# MXM_Connector.net
KiCad netlist of a schematic drawn in Altium Designer
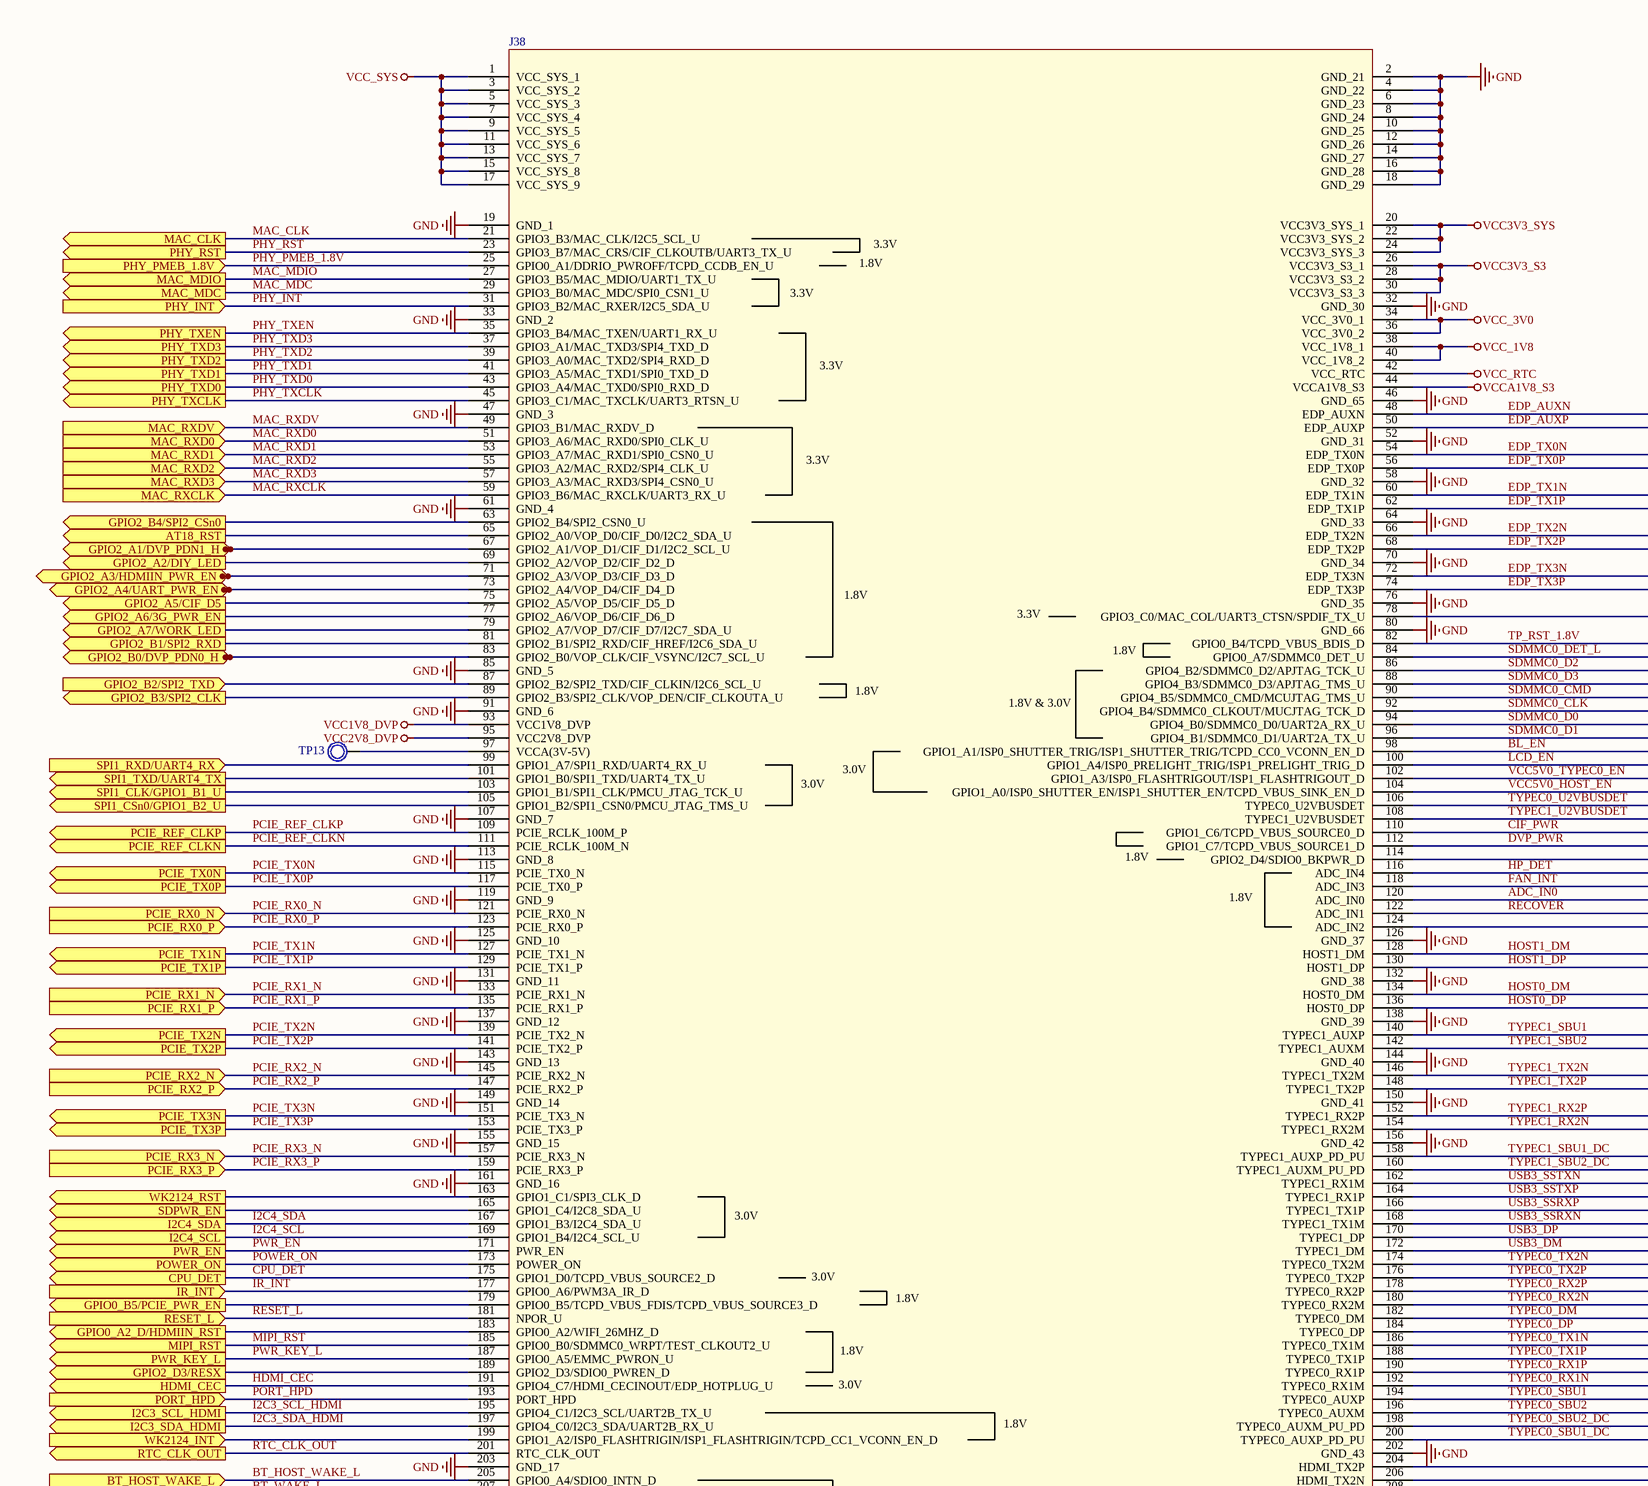
[diagram p0: MXM_Connector.SchDoc, top left]
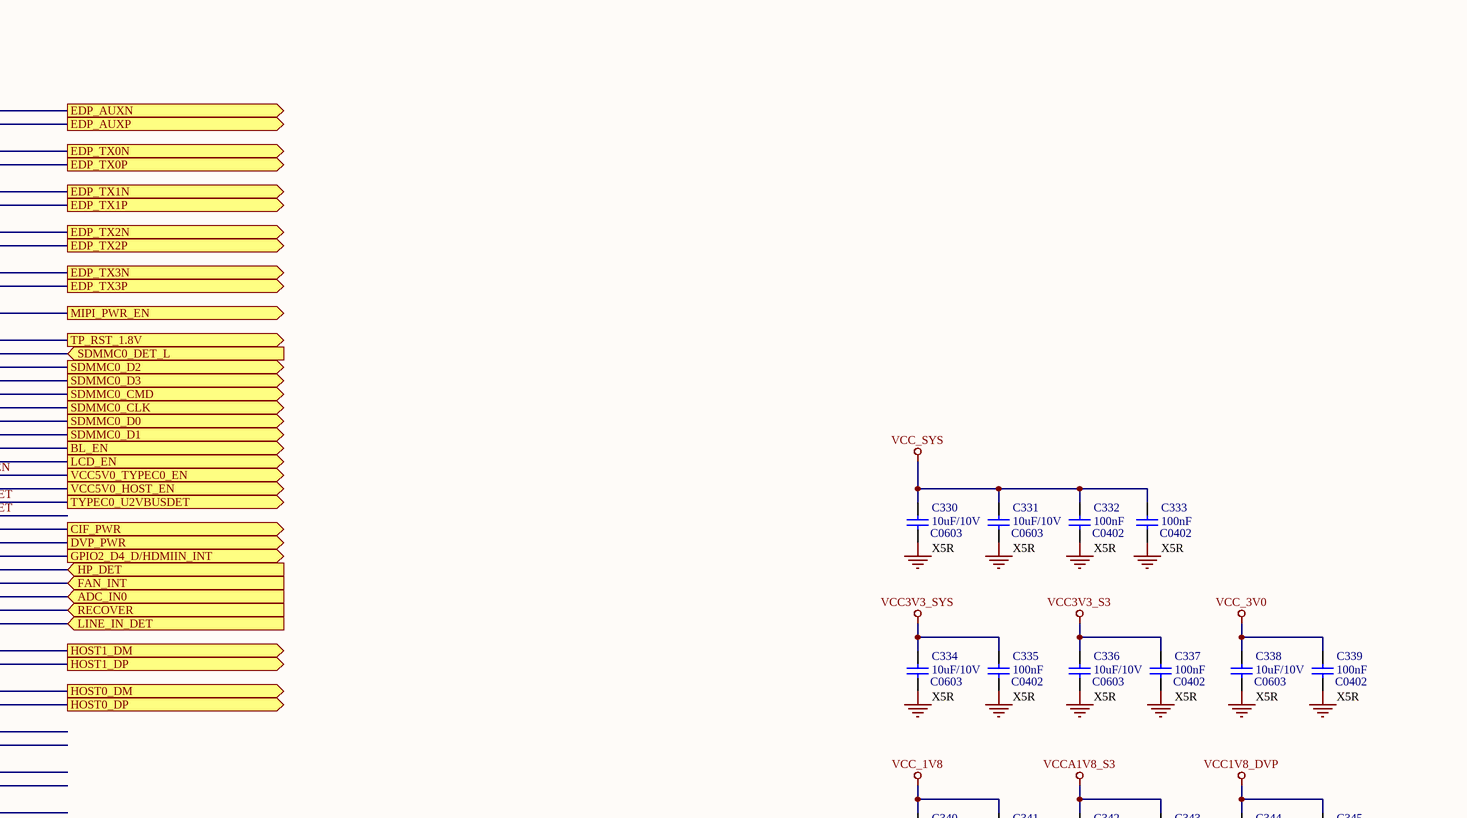
[diagram p1: MXM_Connector.SchDoc, top right]
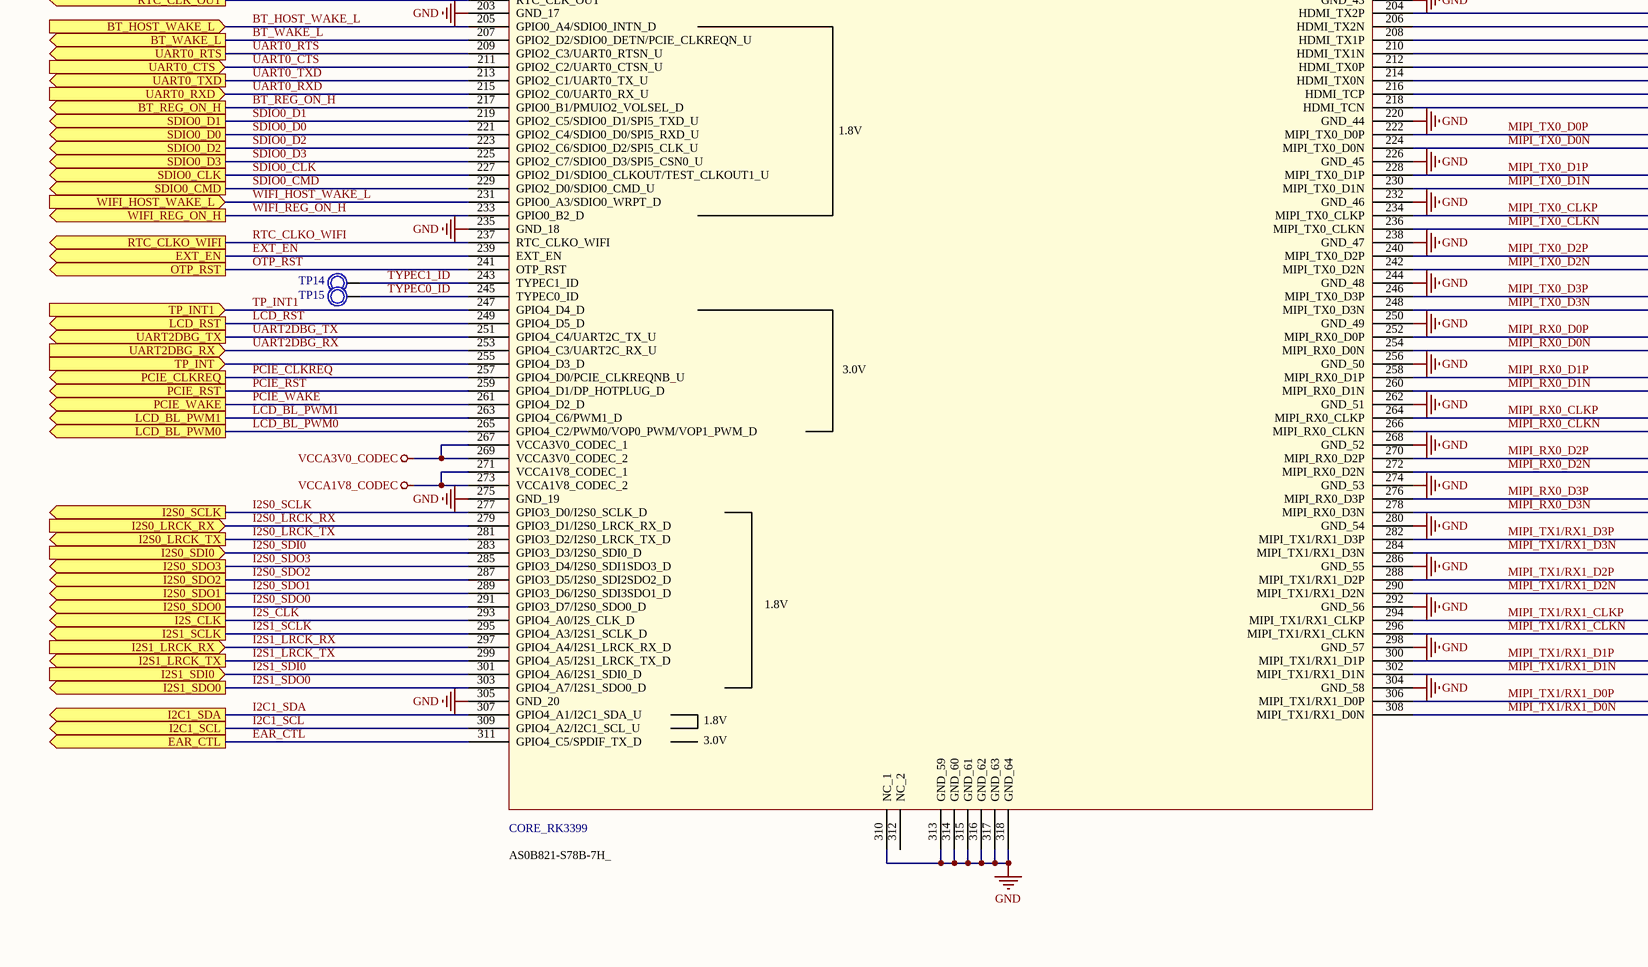
[diagram p2: MXM_Connector.SchDoc, bottom left]
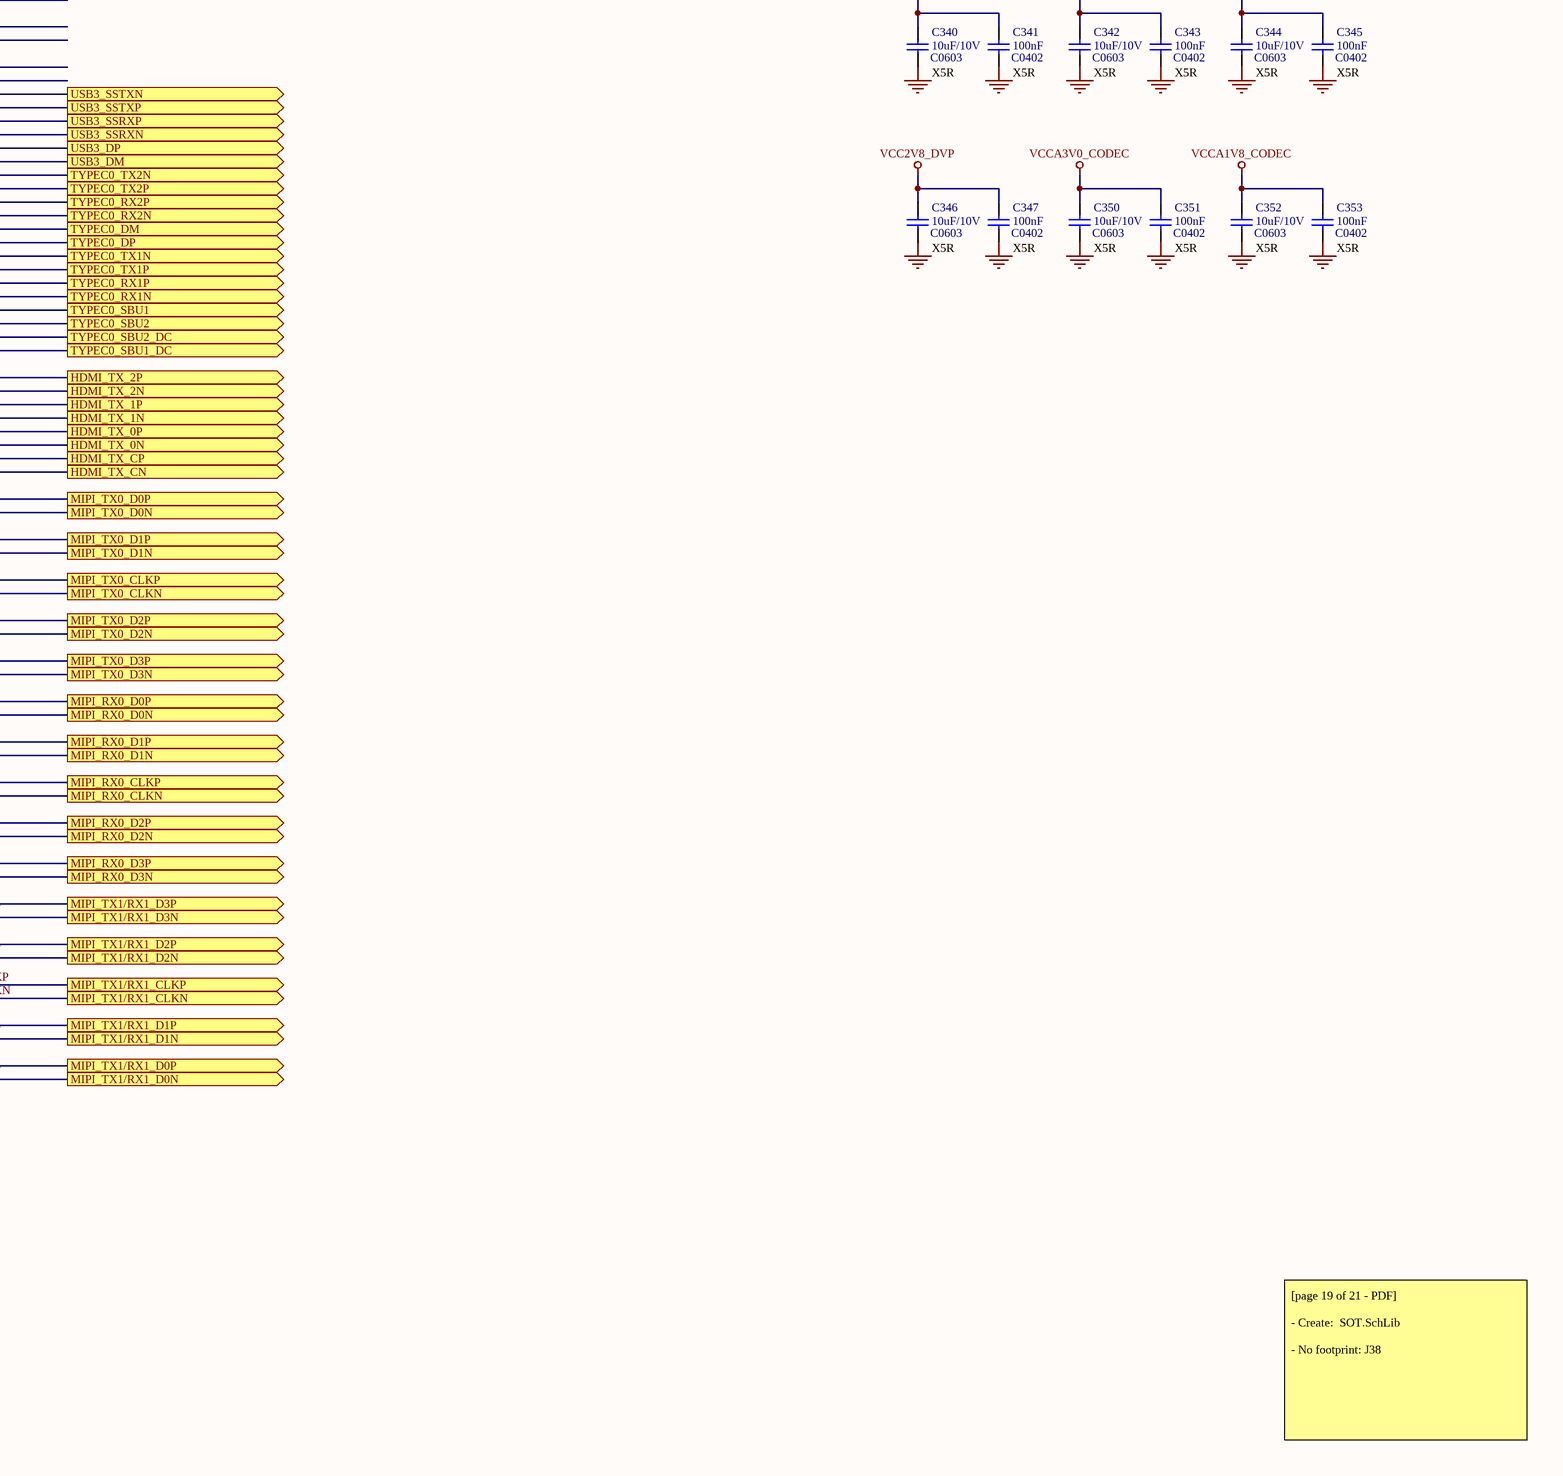
[diagram p3: MXM_Connector.SchDoc, bottom right]

(export (version "E")
  (design (tool "Eeschema 10.0.6"))
  (components
    (comp (ref "C330")
      (value "C0603")
      (footprint "C 0603")
      (description "Capacitor")
      (fields
        (field (name "ALTIUM_VALUE") "10uF/10V")
        (field (name "ALTIUM_UNNAMED_1") "X5R")
        (field (name "PUBLISHER") "Altium Limited")
      )
      (libsource (lib "Miscellaneous Devices") (part "Cap"))
    )
    (comp (ref "C331")
      (value "C0603")
      (footprint "C 0603")
      (description "Capacitor")
      (fields
        (field (name "ALTIUM_VALUE") "10uF/10V")
        (field (name "ALTIUM_UNNAMED_1") "X5R")
        (field (name "PUBLISHER") "Altium Limited")
      )
      (libsource (lib "Miscellaneous Devices") (part "Cap"))
    )
    (comp (ref "C332")
      (value "C0402")
      (footprint "C 0402")
      (description "Capacitor")
      (fields
        (field (name "ALTIUM_VALUE") "100nF")
        (field (name "ALTIUM_UNNAMED_1") "X5R")
        (field (name "PUBLISHER") "Altium Limited")
      )
      (libsource (lib "Miscellaneous Devices") (part "Cap"))
    )
    (comp (ref "C333")
      (value "C0402")
      (footprint "C 0402")
      (description "Capacitor")
      (fields
        (field (name "ALTIUM_VALUE") "100nF")
        (field (name "ALTIUM_UNNAMED_1") "X5R")
        (field (name "PUBLISHER") "Altium Limited")
      )
      (libsource (lib "Miscellaneous Devices") (part "Cap"))
    )
    (comp (ref "C334")
      (value "C0603")
      (footprint "C 0603")
      (description "Capacitor")
      (fields
        (field (name "ALTIUM_VALUE") "10uF/10V")
        (field (name "ALTIUM_UNNAMED_1") "X5R")
        (field (name "PUBLISHER") "Altium Limited")
      )
      (libsource (lib "Miscellaneous Devices") (part "Cap"))
    )
    (comp (ref "C335")
      (value "C0402")
      (footprint "C 0402")
      (description "Capacitor")
      (fields
        (field (name "ALTIUM_VALUE") "100nF")
        (field (name "ALTIUM_UNNAMED_1") "X5R")
        (field (name "PUBLISHER") "Altium Limited")
      )
      (libsource (lib "Miscellaneous Devices") (part "Cap"))
    )
    (comp (ref "C336")
      (value "C0603")
      (footprint "C 0603")
      (description "Capacitor")
      (fields
        (field (name "ALTIUM_VALUE") "10uF/10V")
        (field (name "ALTIUM_UNNAMED_1") "X5R")
        (field (name "PUBLISHER") "Altium Limited")
      )
      (libsource (lib "Miscellaneous Devices") (part "Cap"))
    )
    (comp (ref "C337")
      (value "C0402")
      (footprint "C 0402")
      (description "Capacitor")
      (fields
        (field (name "ALTIUM_VALUE") "100nF")
        (field (name "ALTIUM_UNNAMED_1") "X5R")
        (field (name "PUBLISHER") "Altium Limited")
      )
      (libsource (lib "Miscellaneous Devices") (part "Cap"))
    )
    (comp (ref "C338")
      (value "C0603")
      (footprint "C 0603")
      (description "Capacitor")
      (fields
        (field (name "ALTIUM_VALUE") "10uF/10V")
        (field (name "ALTIUM_UNNAMED_1") "X5R")
        (field (name "PUBLISHER") "Altium Limited")
      )
      (libsource (lib "Miscellaneous Devices") (part "Cap"))
    )
    (comp (ref "C339")
      (value "C0402")
      (footprint "C 0402")
      (description "Capacitor")
      (fields
        (field (name "ALTIUM_VALUE") "100nF")
        (field (name "ALTIUM_UNNAMED_1") "X5R")
        (field (name "PUBLISHER") "Altium Limited")
      )
      (libsource (lib "Miscellaneous Devices") (part "Cap"))
    )
    (comp (ref "C340")
      (value "C0603")
      (footprint "C 0603")
      (description "Capacitor")
      (fields
        (field (name "ALTIUM_VALUE") "10uF/10V")
        (field (name "ALTIUM_UNNAMED_1") "X5R")
        (field (name "PUBLISHER") "Altium Limited")
      )
      (libsource (lib "Miscellaneous Devices") (part "Cap"))
    )
    (comp (ref "C341")
      (value "C0402")
      (footprint "C 0402")
      (description "Capacitor")
      (fields
        (field (name "ALTIUM_VALUE") "100nF")
        (field (name "ALTIUM_UNNAMED_1") "X5R")
        (field (name "PUBLISHER") "Altium Limited")
      )
      (libsource (lib "Miscellaneous Devices") (part "Cap"))
    )
    (comp (ref "C342")
      (value "C0603")
      (footprint "C 0603")
      (description "Capacitor")
      (fields
        (field (name "ALTIUM_VALUE") "10uF/10V")
        (field (name "ALTIUM_UNNAMED_1") "X5R")
        (field (name "PUBLISHER") "Altium Limited")
      )
      (libsource (lib "Miscellaneous Devices") (part "Cap"))
    )
    (comp (ref "C343")
      (value "C0402")
      (footprint "C 0402")
      (description "Capacitor")
      (fields
        (field (name "ALTIUM_VALUE") "100nF")
        (field (name "ALTIUM_UNNAMED_1") "X5R")
        (field (name "PUBLISHER") "Altium Limited")
      )
      (libsource (lib "Miscellaneous Devices") (part "Cap"))
    )
    (comp (ref "C344")
      (value "C0603")
      (footprint "C 0603")
      (description "Capacitor")
      (fields
        (field (name "ALTIUM_VALUE") "10uF/10V")
        (field (name "ALTIUM_UNNAMED_1") "X5R")
        (field (name "PUBLISHER") "Altium Limited")
      )
      (libsource (lib "Miscellaneous Devices") (part "Cap"))
    )
    (comp (ref "C345")
      (value "C0402")
      (footprint "C 0402")
      (description "Capacitor")
      (fields
        (field (name "ALTIUM_VALUE") "100nF")
        (field (name "ALTIUM_UNNAMED_1") "X5R")
        (field (name "PUBLISHER") "Altium Limited")
      )
      (libsource (lib "Miscellaneous Devices") (part "Cap"))
    )
    (comp (ref "C346")
      (value "C0603")
      (footprint "C 0603")
      (description "Capacitor")
      (fields
        (field (name "ALTIUM_VALUE") "10uF/10V")
        (field (name "ALTIUM_UNNAMED_1") "X5R")
        (field (name "PUBLISHER") "Altium Limited")
      )
      (libsource (lib "Miscellaneous Devices") (part "Cap"))
    )
    (comp (ref "C347")
      (value "C0402")
      (footprint "C 0402")
      (description "Capacitor")
      (fields
        (field (name "ALTIUM_VALUE") "100nF")
        (field (name "ALTIUM_UNNAMED_1") "X5R")
        (field (name "PUBLISHER") "Altium Limited")
      )
      (libsource (lib "Miscellaneous Devices") (part "Cap"))
    )
    (comp (ref "C350")
      (value "C0603")
      (footprint "C 0603")
      (description "Capacitor")
      (fields
        (field (name "ALTIUM_VALUE") "10uF/10V")
        (field (name "ALTIUM_UNNAMED_1") "X5R")
        (field (name "PUBLISHER") "Altium Limited")
      )
      (libsource (lib "Miscellaneous Devices") (part "Cap"))
    )
    (comp (ref "C351")
      (value "C0402")
      (footprint "C 0402")
      (description "Capacitor")
      (fields
        (field (name "ALTIUM_VALUE") "100nF")
        (field (name "ALTIUM_UNNAMED_1") "X5R")
        (field (name "PUBLISHER") "Altium Limited")
      )
      (libsource (lib "Miscellaneous Devices") (part "Cap"))
    )
    (comp (ref "C352")
      (value "C0603")
      (footprint "C 0603")
      (description "Capacitor")
      (fields
        (field (name "ALTIUM_VALUE") "10uF/10V")
        (field (name "ALTIUM_UNNAMED_1") "X5R")
        (field (name "PUBLISHER") "Altium Limited")
      )
      (libsource (lib "Miscellaneous Devices") (part "Cap"))
    )
    (comp (ref "C353")
      (value "C0402")
      (footprint "C 0402")
      (description "Capacitor")
      (fields
        (field (name "ALTIUM_VALUE") "100nF")
        (field (name "ALTIUM_UNNAMED_1") "X5R")
        (field (name "PUBLISHER") "Altium Limited")
      )
      (libsource (lib "Miscellaneous Devices") (part "Cap"))
    )
    (comp (ref "J38")
      (value "CORE_RK3399")
      (footprint "*FOX_AS0B821-S78B-7H_AS0B821-S78B-7H(Primary)")
      (fields (field (name "PACKAGE") "AS0B821-S78B-7H_"))
      (libsource (lib "SOT") (part "CORE_RK3399"))
    )
    (comp (ref "TP13")
      (value "TP")
      (footprint "TP1")
      (description "Test Point")
      (libsource (lib "syhaunguyen") (part "TP1"))
    )
    (comp (ref "TP14")
      (value "TP")
      (footprint "TP1")
      (description "Test Point")
      (libsource (lib "syhaunguyen") (part "TP1"))
    )
    (comp (ref "TP15")
      (value "TP")
      (footprint "TP1")
      (description "Test Point")
      (libsource (lib "syhaunguyen") (part "TP1"))
    )
  )
  (nets
    (net (code "1") (name "/ADC_IN0") (class "Default")
      (node (ref "J38") (pin "120") (pinfunction "ADC_IN0_120") (pintype "passive"))
    )
    (net (code "2") (name "/AT18_RST") (class "Default")
      (node (ref "J38") (pin "65") (pinfunction "GPIO2_A0/VOP_D0/CIF_D0/I2C2_SDA_U_65") (pintype "passive"))
    )
    (net (code "3") (name "/BL_EN") (class "Default")
      (node (ref "J38") (pin "98") (pinfunction "GPIO1_A1/ISP0_SHUTTER_TRIG/ISP1_SHUTTER_TRIG/TCPD_CC0_VCONN_EN_D_98") (pintype "passive"))
    )
    (net (code "4") (name "/BT_HOST_WAKE_L") (class "Default")
      (node (ref "J38") (pin "205") (pinfunction "GPIO0_A4/SDIO0_INTN_D_205") (pintype "passive"))
    )
    (net (code "5") (name "/BT_REG_ON_H") (class "Default")
      (node (ref "J38") (pin "217") (pinfunction "GPIO0_B1/PMUIO2_VOLSEL_D_217") (pintype "passive"))
    )
    (net (code "6") (name "/BT_WAKE_L") (class "Default")
      (node (ref "J38") (pin "207") (pinfunction "GPIO2_D2/SDIO0_DETN/PCIE_CLKREQN_U_207") (pintype "passive"))
    )
    (net (code "7") (name "/CIF_PWR") (class "Default")
      (node (ref "J38") (pin "110") (pinfunction "GPIO1_C6/TCPD_VBUS_SOURCE0_D_110") (pintype "passive"))
    )
    (net (code "8") (name "/CPU_DET") (class "Default")
      (node (ref "J38") (pin "175") (pinfunction "GPIO1_D0/TCPD_VBUS_SOURCE2_D_175") (pintype "passive"))
    )
    (net (code "9") (name "/DVP_PWR") (class "Default")
      (node (ref "J38") (pin "112") (pinfunction "GPIO1_C7/TCPD_VBUS_SOURCE1_D_112") (pintype "passive"))
    )
    (net (code "10") (name "/EAR_CTL") (class "Default")
      (node (ref "J38") (pin "311") (pinfunction "GPIO4_C5/SPDIF_TX_D_311") (pintype "passive"))
    )
    (net (code "11") (name "/EDP_AUXN") (class "Default")
      (node (ref "J38") (pin "48") (pinfunction "EDP_AUXN_48") (pintype "passive"))
    )
    (net (code "12") (name "/EDP_AUXP") (class "Default")
      (node (ref "J38") (pin "50") (pinfunction "EDP_AUXP_50") (pintype "passive"))
    )
    (net (code "13") (name "/EDP_TX0N") (class "Default")
      (node (ref "J38") (pin "54") (pinfunction "EDP_TX0N_54") (pintype "passive"))
    )
    (net (code "14") (name "/EDP_TX0P") (class "Default")
      (node (ref "J38") (pin "56") (pinfunction "EDP_TX0P_56") (pintype "passive"))
    )
    (net (code "15") (name "/EDP_TX1N") (class "Default")
      (node (ref "J38") (pin "60") (pinfunction "EDP_TX1N_60") (pintype "passive"))
    )
    (net (code "16") (name "/EDP_TX1P") (class "Default")
      (node (ref "J38") (pin "62") (pinfunction "EDP_TX1P_62") (pintype "passive"))
    )
    (net (code "17") (name "/EDP_TX2N") (class "Default")
      (node (ref "J38") (pin "66") (pinfunction "EDP_TX2N_66") (pintype "passive"))
    )
    (net (code "18") (name "/EDP_TX2P") (class "Default")
      (node (ref "J38") (pin "68") (pinfunction "EDP_TX2P_68") (pintype "passive"))
    )
    (net (code "19") (name "/EDP_TX3N") (class "Default")
      (node (ref "J38") (pin "72") (pinfunction "EDP_TX3N_72") (pintype "passive"))
    )
    (net (code "20") (name "/EDP_TX3P") (class "Default")
      (node (ref "J38") (pin "74") (pinfunction "EDP_TX3P_74") (pintype "passive"))
    )
    (net (code "21") (name "/EXT_EN") (class "Default")
      (node (ref "J38") (pin "239") (pinfunction "EXT_EN_239") (pintype "passive"))
    )
    (net (code "22") (name "/FAN_INT") (class "Default")
      (node (ref "J38") (pin "118") (pinfunction "ADC_IN3_118") (pintype "passive"))
    )
    (net (code "23") (name "/GPIO0_A2_D{slash}HDMIIN_RST") (class "Default")
      (node (ref "J38") (pin "183") (pinfunction "GPIO0_A2/WIFI_26MHZ_D_183") (pintype "passive"))
    )
    (net (code "24") (name "/GPIO0_B5{slash}PCIE_PWR_EN") (class "Default")
      (node (ref "J38") (pin "179") (pinfunction "GPIO0_B5/TCPD_VBUS_FDIS/TCPD_VBUS_SOURCE3_D_179") (pintype "passive"))
    )
    (net (code "25") (name "/GPIO2_A1{slash}DVP_PDN1_H") (class "Default")
      (node (ref "J38") (pin "67") (pinfunction "GPIO2_A1/VOP_D1/CIF_D1/I2C2_SCL_U_67") (pintype "passive"))
    )
    (net (code "26") (name "/GPIO2_A2{slash}DIY_LED") (class "Default")
      (node (ref "J38") (pin "69") (pinfunction "GPIO2_A2/VOP_D2/CIF_D2_D_69") (pintype "passive"))
    )
    (net (code "27") (name "/GPIO2_A3{slash}HDMIIN_PWR_EN") (class "Default")
      (node (ref "J38") (pin "71") (pinfunction "GPIO2_A3/VOP_D3/CIF_D3_D_71") (pintype "passive"))
    )
    (net (code "28") (name "/GPIO2_A4{slash}UART_PWR_EN") (class "Default")
      (node (ref "J38") (pin "73") (pinfunction "GPIO2_A4/VOP_D4/CIF_D4_D_73") (pintype "passive"))
    )
    (net (code "29") (name "/GPIO2_A5{slash}CIF_D5") (class "Default")
      (node (ref "J38") (pin "75") (pinfunction "GPIO2_A5/VOP_D5/CIF_D5_D_75") (pintype "passive"))
    )
    (net (code "30") (name "/GPIO2_A6{slash}3G_PWR_EN") (class "Default")
      (node (ref "J38") (pin "77") (pinfunction "GPIO2_A6/VOP_D6/CIF_D6_D_77") (pintype "passive"))
    )
    (net (code "31") (name "/GPIO2_A7{slash}WORK_LED") (class "Default")
      (node (ref "J38") (pin "79") (pinfunction "GPIO2_A7/VOP_D7/CIF_D7/I2C7_SDA_U_79") (pintype "passive"))
    )
    (net (code "32") (name "/GPIO2_B0{slash}DVP_PDN0_H") (class "Default")
      (node (ref "J38") (pin "83") (pinfunction "GPIO2_B0/VOP_CLK/CIF_VSYNC/I2C7_SCL_U_83") (pintype "passive"))
    )
    (net (code "33") (name "/GPIO2_B1{slash}SPI2_RXD") (class "Default")
      (node (ref "J38") (pin "81") (pinfunction "GPIO2_B1/SPI2_RXD/CIF_HREF/I2C6_SDA_U_81") (pintype "passive"))
    )
    (net (code "34") (name "/GPIO2_B2{slash}SPI2_TXD") (class "Default")
      (node (ref "J38") (pin "87") (pinfunction "GPIO2_B2/SPI2_TXD/CIF_CLKIN/I2C6_SCL_U_87") (pintype "passive"))
    )
    (net (code "35") (name "/GPIO2_B3{slash}SPI2_CLK") (class "Default")
      (node (ref "J38") (pin "89") (pinfunction "GPIO2_B3/SPI2_CLK/VOP_DEN/CIF_CLKOUTA_U_89") (pintype "passive"))
    )
    (net (code "36") (name "/GPIO2_B4{slash}SPI2_CSn0") (class "Default")
      (node (ref "J38") (pin "63") (pinfunction "GPIO2_B4/SPI2_CSN0_U_63") (pintype "passive"))
    )
    (net (code "37") (name "/GPIO2_D3{slash}RESX") (class "Default")
      (node (ref "J38") (pin "189") (pinfunction "GPIO2_D3/SDIO0_PWREN_D_189") (pintype "passive"))
    )
    (net (code "38") (name "/GPIO2_D4_D{slash}HDMIIN_INT") (class "Default")
      (node (ref "J38") (pin "114") (pinfunction "GPIO2_D4/SDIO0_BKPWR_D_114") (pintype "passive"))
    )
    (net (code "39") (name "/HDMI_CEC") (class "Default")
      (node (ref "J38") (pin "191") (pinfunction "GPIO4_C7/HDMI_CECINOUT/EDP_HOTPLUG_U_191") (pintype "passive"))
    )
    (net (code "40") (name "/HDMI_TX_0N") (class "Default")
      (node (ref "J38") (pin "214") (pinfunction "HDMI_TX0N_214") (pintype "passive"))
    )
    (net (code "41") (name "/HDMI_TX_0P") (class "Default")
      (node (ref "J38") (pin "212") (pinfunction "HDMI_TX0P_212") (pintype "passive"))
    )
    (net (code "42") (name "/HDMI_TX_1N") (class "Default")
      (node (ref "J38") (pin "210") (pinfunction "HDMI_TX1N_210") (pintype "passive"))
    )
    (net (code "43") (name "/HDMI_TX_1P") (class "Default")
      (node (ref "J38") (pin "208") (pinfunction "HDMI_TX1P_208") (pintype "passive"))
    )
    (net (code "44") (name "/HDMI_TX_2N") (class "Default")
      (node (ref "J38") (pin "206") (pinfunction "HDMI_TX2N_206") (pintype "passive"))
    )
    (net (code "45") (name "/HDMI_TX_2P") (class "Default")
      (node (ref "J38") (pin "204") (pinfunction "HDMI_TX2P_204") (pintype "passive"))
    )
    (net (code "46") (name "/HDMI_TX_CN") (class "Default")
      (node (ref "J38") (pin "218") (pinfunction "HDMI_TCN_218") (pintype "passive"))
    )
    (net (code "47") (name "/HDMI_TX_CP") (class "Default")
      (node (ref "J38") (pin "216") (pinfunction "HDMI_TCP_216") (pintype "passive"))
    )
    (net (code "48") (name "/HOST0_DM") (class "Default")
      (node (ref "J38") (pin "134") (pinfunction "HOST0_DM_134") (pintype "passive"))
    )
    (net (code "49") (name "/HOST0_DP") (class "Default")
      (node (ref "J38") (pin "136") (pinfunction "HOST0_DP_136") (pintype "passive"))
    )
    (net (code "50") (name "/HOST1_DM") (class "Default")
      (node (ref "J38") (pin "128") (pinfunction "HOST1_DM_128") (pintype "passive"))
    )
    (net (code "51") (name "/HOST1_DP") (class "Default")
      (node (ref "J38") (pin "130") (pinfunction "HOST1_DP_130") (pintype "passive"))
    )
    (net (code "52") (name "/HP_DET") (class "Default")
      (node (ref "J38") (pin "116") (pinfunction "ADC_IN4_116") (pintype "passive"))
    )
    (net (code "53") (name "/I2C1_SCL") (class "Default")
      (node (ref "J38") (pin "309") (pinfunction "GPIO4_A2/I2C1_SCL_U_309") (pintype "passive"))
    )
    (net (code "54") (name "/I2C1_SDA") (class "Default")
      (node (ref "J38") (pin "307") (pinfunction "GPIO4_A1/I2C1_SDA_U_307") (pintype "passive"))
    )
    (net (code "55") (name "/I2C3_SCL_HDMI") (class "Default")
      (node (ref "J38") (pin "195") (pinfunction "GPIO4_C1/I2C3_SCL/UART2B_TX_U_195") (pintype "passive"))
    )
    (net (code "56") (name "/I2C3_SDA_HDMI") (class "Default")
      (node (ref "J38") (pin "197") (pinfunction "GPIO4_C0/I2C3_SDA/UART2B_RX_U_197") (pintype "passive"))
    )
    (net (code "57") (name "/I2C4_SCL") (class "Default")
      (node (ref "J38") (pin "169") (pinfunction "GPIO1_B4/I2C4_SCL_U_169") (pintype "passive"))
    )
    (net (code "58") (name "/I2C4_SDA") (class "Default")
      (node (ref "J38") (pin "167") (pinfunction "GPIO1_B3/I2C4_SDA_U_167") (pintype "passive"))
    )
    (net (code "59") (name "/I2S0_LRCK_RX") (class "Default")
      (node (ref "J38") (pin "279") (pinfunction "GPIO3_D1/I2S0_LRCK_RX_D_279") (pintype "passive"))
    )
    (net (code "60") (name "/I2S0_LRCK_TX") (class "Default")
      (node (ref "J38") (pin "281") (pinfunction "GPIO3_D2/I2S0_LRCK_TX_D_281") (pintype "passive"))
    )
    (net (code "61") (name "/I2S0_SCLK") (class "Default")
      (node (ref "J38") (pin "277") (pinfunction "GPIO3_D0/I2S0_SCLK_D_277") (pintype "passive"))
    )
    (net (code "62") (name "/I2S0_SDI0") (class "Default")
      (node (ref "J38") (pin "283") (pinfunction "GPIO3_D3/I2S0_SDI0_D_283") (pintype "passive"))
    )
    (net (code "63") (name "/I2S0_SDO0") (class "Default")
      (node (ref "J38") (pin "291") (pinfunction "GPIO3_D7/I2S0_SDO0_D_291") (pintype "passive"))
    )
    (net (code "64") (name "/I2S0_SDO1") (class "Default")
      (node (ref "J38") (pin "289") (pinfunction "GPIO3_D6/I2S0_SDI3SDO1_D_289") (pintype "passive"))
    )
    (net (code "65") (name "/I2S0_SDO2") (class "Default")
      (node (ref "J38") (pin "287") (pinfunction "GPIO3_D5/I2S0_SDI2SDO2_D_287") (pintype "passive"))
    )
    (net (code "66") (name "/I2S0_SDO3") (class "Default")
      (node (ref "J38") (pin "285") (pinfunction "GPIO3_D4/I2S0_SDI1SDO3_D_285") (pintype "passive"))
    )
    (net (code "67") (name "/I2S1_LRCK_RX") (class "Default")
      (node (ref "J38") (pin "297") (pinfunction "GPIO4_A4/I2S1_LRCK_RX_D_297") (pintype "passive"))
    )
    (net (code "68") (name "/I2S1_LRCK_TX") (class "Default")
      (node (ref "J38") (pin "299") (pinfunction "GPIO4_A5/I2S1_LRCK_TX_D_299") (pintype "passive"))
    )
    (net (code "69") (name "/I2S1_SCLK") (class "Default")
      (node (ref "J38") (pin "295") (pinfunction "GPIO4_A3/I2S1_SCLK_D_295") (pintype "passive"))
    )
    (net (code "70") (name "/I2S1_SDI0") (class "Default")
      (node (ref "J38") (pin "301") (pinfunction "GPIO4_A6/I2S1_SDI0_D_301") (pintype "passive"))
    )
    (net (code "71") (name "/I2S1_SDO0") (class "Default")
      (node (ref "J38") (pin "303") (pinfunction "GPIO4_A7/I2S1_SDO0_D_303") (pintype "passive"))
    )
    (net (code "72") (name "/I2S_CLK") (class "Default")
      (node (ref "J38") (pin "293") (pinfunction "GPIO4_A0/I2S_CLK_D_293") (pintype "passive"))
    )
    (net (code "73") (name "/IR_INT") (class "Default")
      (node (ref "J38") (pin "177") (pinfunction "GPIO0_A6/PWM3A_IR_D_177") (pintype "passive"))
    )
    (net (code "74") (name "/LCD_BL_PWM0") (class "Default")
      (node (ref "J38") (pin "265") (pinfunction "GPIO4_C2/PWM0/VOP0_PWM/VOP1_PWM_D_265") (pintype "passive"))
    )
    (net (code "75") (name "/LCD_BL_PWM1") (class "Default")
      (node (ref "J38") (pin "263") (pinfunction "GPIO4_C6/PWM1_D_263") (pintype "passive"))
    )
    (net (code "76") (name "/LCD_EN") (class "Default")
      (node (ref "J38") (pin "100") (pinfunction "GPIO1_A4/ISP0_PRELIGHT_TRIG/ISP1_PRELIGHT_TRIG_D_100") (pintype "passive"))
    )
    (net (code "77") (name "/LCD_RST") (class "Default")
      (node (ref "J38") (pin "249") (pinfunction "GPIO4_D5_D_249") (pintype "passive"))
    )
    (net (code "78") (name "/LINE_IN_DET") (class "Default")
      (node (ref "J38") (pin "124") (pinfunction "ADC_IN2_124") (pintype "passive"))
    )
    (net (code "79") (name "/MAC_CLK") (class "Default")
      (node (ref "J38") (pin "21") (pinfunction "GPIO3_B3/MAC_CLK/I2C5_SCL_U_21") (pintype "passive"))
    )
    (net (code "80") (name "/MAC_MDC") (class "Default")
      (node (ref "J38") (pin "29") (pinfunction "GPIO3_B0/MAC_MDC/SPI0_CSN1_U_29") (pintype "passive"))
    )
    (net (code "81") (name "/MAC_MDIO") (class "Default")
      (node (ref "J38") (pin "27") (pinfunction "GPIO3_B5/MAC_MDIO/UART1_TX_U_27") (pintype "passive"))
    )
    (net (code "82") (name "/MAC_RXCLK") (class "Default")
      (node (ref "J38") (pin "59") (pinfunction "GPIO3_B6/MAC_RXCLK/UART3_RX_U_59") (pintype "passive"))
    )
    (net (code "83") (name "/MAC_RXD0") (class "Default")
      (node (ref "J38") (pin "51") (pinfunction "GPIO3_A6/MAC_RXD0/SPI0_CLK_U_51") (pintype "passive"))
    )
    (net (code "84") (name "/MAC_RXD1") (class "Default")
      (node (ref "J38") (pin "53") (pinfunction "GPIO3_A7/MAC_RXD1/SPI0_CSN0_U_53") (pintype "passive"))
    )
    (net (code "85") (name "/MAC_RXD2") (class "Default")
      (node (ref "J38") (pin "55") (pinfunction "GPIO3_A2/MAC_RXD2/SPI4_CLK_U_55") (pintype "passive"))
    )
    (net (code "86") (name "/MAC_RXD3") (class "Default")
      (node (ref "J38") (pin "57") (pinfunction "GPIO3_A3/MAC_RXD3/SPI4_CSN0_U_57") (pintype "passive"))
    )
    (net (code "87") (name "/MAC_RXDV") (class "Default")
      (node (ref "J38") (pin "49") (pinfunction "GPIO3_B1/MAC_RXDV_D_49") (pintype "passive"))
    )
    (net (code "88") (name "/MIPI_PWR_EN") (class "Default")
      (node (ref "J38") (pin "78") (pinfunction "GPIO3_C0/MAC_COL/UART3_CTSN/SPDIF_TX_U_78") (pintype "passive"))
    )
    (net (code "89") (name "/MIPI_RST") (class "Default")
      (node (ref "J38") (pin "185") (pinfunction "GPIO0_B0/SDMMC0_WRPT/TEST_CLKOUT2_U_185") (pintype "passive"))
    )
    (net (code "90") (name "/MIPI_RX0_CLKN") (class "Default")
      (node (ref "J38") (pin "266") (pinfunction "MIPI_RX0_CLKN_266") (pintype "passive"))
    )
    (net (code "91") (name "/MIPI_RX0_CLKP") (class "Default")
      (node (ref "J38") (pin "264") (pinfunction "MIPI_RX0_CLKP_264") (pintype "passive"))
    )
    (net (code "92") (name "/MIPI_RX0_D0N") (class "Default")
      (node (ref "J38") (pin "254") (pinfunction "MIPI_RX0_D0N_254") (pintype "passive"))
    )
    (net (code "93") (name "/MIPI_RX0_D0P") (class "Default")
      (node (ref "J38") (pin "252") (pinfunction "MIPI_RX0_D0P_252") (pintype "passive"))
    )
    (net (code "94") (name "/MIPI_RX0_D1N") (class "Default")
      (node (ref "J38") (pin "260") (pinfunction "MIPI_RX0_D1N_260") (pintype "passive"))
    )
    (net (code "95") (name "/MIPI_RX0_D1P") (class "Default")
      (node (ref "J38") (pin "258") (pinfunction "MIPI_RX0_D1P_258") (pintype "passive"))
    )
    (net (code "96") (name "/MIPI_RX0_D2N") (class "Default")
      (node (ref "J38") (pin "272") (pinfunction "MIPI_RX0_D2N_272") (pintype "passive"))
    )
    (net (code "97") (name "/MIPI_RX0_D2P") (class "Default")
      (node (ref "J38") (pin "270") (pinfunction "MIPI_RX0_D2P_270") (pintype "passive"))
    )
    (net (code "98") (name "/MIPI_RX0_D3N") (class "Default")
      (node (ref "J38") (pin "278") (pinfunction "MIPI_RX0_D3N_278") (pintype "passive"))
    )
    (net (code "99") (name "/MIPI_RX0_D3P") (class "Default")
      (node (ref "J38") (pin "276") (pinfunction "MIPI_RX0_D3P_276") (pintype "passive"))
    )
    (net (code "100") (name "/MIPI_TX0_CLKN") (class "Default")
      (node (ref "J38") (pin "236") (pinfunction "MIPI_TX0_CLKN_236") (pintype "passive"))
    )
    (net (code "101") (name "/MIPI_TX0_CLKP") (class "Default")
      (node (ref "J38") (pin "234") (pinfunction "MIPI_TX0_CLKP_234") (pintype "passive"))
    )
    (net (code "102") (name "/MIPI_TX0_D0N") (class "Default")
      (node (ref "J38") (pin "224") (pinfunction "MIPI_TX0_D0N_224") (pintype "passive"))
    )
    (net (code "103") (name "/MIPI_TX0_D0P") (class "Default")
      (node (ref "J38") (pin "222") (pinfunction "MIPI_TX0_D0P_222") (pintype "passive"))
    )
    (net (code "104") (name "/MIPI_TX0_D1N") (class "Default")
      (node (ref "J38") (pin "230") (pinfunction "MIPI_TX0_D1N_230") (pintype "passive"))
    )
    (net (code "105") (name "/MIPI_TX0_D1P") (class "Default")
      (node (ref "J38") (pin "228") (pinfunction "MIPI_TX0_D1P_228") (pintype "passive"))
    )
    (net (code "106") (name "/MIPI_TX0_D2N") (class "Default")
      (node (ref "J38") (pin "242") (pinfunction "MIPI_TX0_D2N_242") (pintype "passive"))
    )
    (net (code "107") (name "/MIPI_TX0_D2P") (class "Default")
      (node (ref "J38") (pin "240") (pinfunction "MIPI_TX0_D2P_240") (pintype "passive"))
    )
    (net (code "108") (name "/MIPI_TX0_D3N") (class "Default")
      (node (ref "J38") (pin "248") (pinfunction "MIPI_TX0_D3N_248") (pintype "passive"))
    )
    (net (code "109") (name "/MIPI_TX0_D3P") (class "Default")
      (node (ref "J38") (pin "246") (pinfunction "MIPI_TX0_D3P_246") (pintype "passive"))
    )
    (net (code "110") (name "/MIPI_TX1{slash}RX1_CLKN") (class "Default")
      (node (ref "J38") (pin "296") (pinfunction "MIPI_TX1/RX1_CLKN_296") (pintype "passive"))
    )
    (net (code "111") (name "/MIPI_TX1{slash}RX1_CLKP") (class "Default")
      (node (ref "J38") (pin "294") (pinfunction "MIPI_TX1/RX1_CLKP_294") (pintype "passive"))
    )
    (net (code "112") (name "/MIPI_TX1{slash}RX1_D0N") (class "Default")
      (node (ref "J38") (pin "308") (pinfunction "MIPI_TX1/RX1_D0N_308") (pintype "passive"))
    )
    (net (code "113") (name "/MIPI_TX1{slash}RX1_D0P") (class "Default")
      (node (ref "J38") (pin "306") (pinfunction "MIPI_TX1/RX1_D0P_306") (pintype "passive"))
    )
    (net (code "114") (name "/MIPI_TX1{slash}RX1_D1N") (class "Default")
      (node (ref "J38") (pin "302") (pinfunction "MIPI_TX1/RX1_D1N_302") (pintype "passive"))
    )
    (net (code "115") (name "/MIPI_TX1{slash}RX1_D1P") (class "Default")
      (node (ref "J38") (pin "300") (pinfunction "MIPI_TX1/RX1_D1P_300") (pintype "passive"))
    )
    (net (code "116") (name "/MIPI_TX1{slash}RX1_D2N") (class "Default")
      (node (ref "J38") (pin "290") (pinfunction "MIPI_TX1/RX1_D2N_290") (pintype "passive"))
    )
    (net (code "117") (name "/MIPI_TX1{slash}RX1_D2P") (class "Default")
      (node (ref "J38") (pin "288") (pinfunction "MIPI_TX1/RX1_D2P_288") (pintype "passive"))
    )
    (net (code "118") (name "/MIPI_TX1{slash}RX1_D3N") (class "Default")
      (node (ref "J38") (pin "284") (pinfunction "MIPI_TX1/RX1_D3N_284") (pintype "passive"))
    )
    (net (code "119") (name "/MIPI_TX1{slash}RX1_D3P") (class "Default")
      (node (ref "J38") (pin "282") (pinfunction "MIPI_TX1/RX1_D3P_282") (pintype "passive"))
    )
    (net (code "120") (name "/OTP_RST") (class "Default")
      (node (ref "J38") (pin "241") (pinfunction "OTP_RST_241") (pintype "passive"))
    )
    (net (code "121") (name "/PCIE_CLKREQ") (class "Default")
      (node (ref "J38") (pin "257") (pinfunction "GPIO4_D0/PCIE_CLKREQNB_U_257") (pintype "passive"))
    )
    (net (code "122") (name "/PCIE_REF_CLKN") (class "Default")
      (node (ref "J38") (pin "111") (pinfunction "PCIE_RCLK_100M_N_111") (pintype "passive"))
    )
    (net (code "123") (name "/PCIE_REF_CLKP") (class "Default")
      (node (ref "J38") (pin "109") (pinfunction "PCIE_RCLK_100M_P_109") (pintype "passive"))
    )
    (net (code "124") (name "/PCIE_RST") (class "Default")
      (node (ref "J38") (pin "259") (pinfunction "GPIO4_D1/DP_HOTPLUG_D_259") (pintype "passive"))
    )
    (net (code "125") (name "/PCIE_RX0_N") (class "Default")
      (node (ref "J38") (pin "121") (pinfunction "PCIE_RX0_N_121") (pintype "passive"))
    )
    (net (code "126") (name "/PCIE_RX0_P") (class "Default")
      (node (ref "J38") (pin "123") (pinfunction "PCIE_RX0_P_123") (pintype "passive"))
    )
    (net (code "127") (name "/PCIE_RX1_N") (class "Default")
      (node (ref "J38") (pin "133") (pinfunction "PCIE_RX1_N_133") (pintype "passive"))
    )
    (net (code "128") (name "/PCIE_RX1_P") (class "Default")
      (node (ref "J38") (pin "135") (pinfunction "PCIE_RX1_P_135") (pintype "passive"))
    )
    (net (code "129") (name "/PCIE_RX2_N") (class "Default")
      (node (ref "J38") (pin "145") (pinfunction "PCIE_RX2_N_145") (pintype "passive"))
    )
    (net (code "130") (name "/PCIE_RX2_P") (class "Default")
      (node (ref "J38") (pin "147") (pinfunction "PCIE_RX2_P_147") (pintype "passive"))
    )
    (net (code "131") (name "/PCIE_RX3_N") (class "Default")
      (node (ref "J38") (pin "157") (pinfunction "PCIE_RX3_N_157") (pintype "passive"))
    )
    (net (code "132") (name "/PCIE_RX3_P") (class "Default")
      (node (ref "J38") (pin "159") (pinfunction "PCIE_RX3_P_159") (pintype "passive"))
    )
    (net (code "133") (name "/PCIE_TX0N") (class "Default")
      (node (ref "J38") (pin "115") (pinfunction "PCIE_TX0_N_115") (pintype "passive"))
    )
    (net (code "134") (name "/PCIE_TX0P") (class "Default")
      (node (ref "J38") (pin "117") (pinfunction "PCIE_TX0_P_117") (pintype "passive"))
    )
    (net (code "135") (name "/PCIE_TX1N") (class "Default")
      (node (ref "J38") (pin "127") (pinfunction "PCIE_TX1_N_127") (pintype "passive"))
    )
    (net (code "136") (name "/PCIE_TX1P") (class "Default")
      (node (ref "J38") (pin "129") (pinfunction "PCIE_TX1_P_129") (pintype "passive"))
    )
    (net (code "137") (name "/PCIE_TX2N") (class "Default")
      (node (ref "J38") (pin "139") (pinfunction "PCIE_TX2_N_139") (pintype "passive"))
    )
    (net (code "138") (name "/PCIE_TX2P") (class "Default")
      (node (ref "J38") (pin "141") (pinfunction "PCIE_TX2_P_141") (pintype "passive"))
    )
    (net (code "139") (name "/PCIE_TX3N") (class "Default")
      (node (ref "J38") (pin "151") (pinfunction "PCIE_TX3_N_151") (pintype "passive"))
    )
    (net (code "140") (name "/PCIE_TX3P") (class "Default")
      (node (ref "J38") (pin "153") (pinfunction "PCIE_TX3_P_153") (pintype "passive"))
    )
    (net (code "141") (name "/PCIE_WAKE") (class "Default")
      (node (ref "J38") (pin "261") (pinfunction "GPIO4_D2_D_261") (pintype "passive"))
    )
    (net (code "142") (name "/PHY_INT") (class "Default")
      (node (ref "J38") (pin "31") (pinfunction "GPIO3_B2/MAC_RXER/I2C5_SDA_U_31") (pintype "passive"))
    )
    (net (code "143") (name "/PHY_PMEB_1.8V") (class "Default")
      (node (ref "J38") (pin "25") (pinfunction "GPIO0_A1/DDRIO_PWROFF/TCPD_CCDB_EN_U_25") (pintype "passive"))
    )
    (net (code "144") (name "/PHY_RST") (class "Default")
      (node (ref "J38") (pin "23") (pinfunction "GPIO3_B7/MAC_CRS/CIF_CLKOUTB/UART3_TX_U_23") (pintype "passive"))
    )
    (net (code "145") (name "/PHY_TXCLK") (class "Default")
      (node (ref "J38") (pin "45") (pinfunction "GPIO3_C1/MAC_TXCLK/UART3_RTSN_U_45") (pintype "passive"))
    )
    (net (code "146") (name "/PHY_TXD0") (class "Default")
      (node (ref "J38") (pin "43") (pinfunction "GPIO3_A4/MAC_TXD0/SPI0_RXD_D_43") (pintype "passive"))
    )
    (net (code "147") (name "/PHY_TXD1") (class "Default")
      (node (ref "J38") (pin "41") (pinfunction "GPIO3_A5/MAC_TXD1/SPI0_TXD_D_41") (pintype "passive"))
    )
    (net (code "148") (name "/PHY_TXD2") (class "Default")
      (node (ref "J38") (pin "39") (pinfunction "GPIO3_A0/MAC_TXD2/SPI4_RXD_D_39") (pintype "passive"))
    )
    (net (code "149") (name "/PHY_TXD3") (class "Default")
      (node (ref "J38") (pin "37") (pinfunction "GPIO3_A1/MAC_TXD3/SPI4_TXD_D_37") (pintype "passive"))
    )
    (net (code "150") (name "/PHY_TXEN") (class "Default")
      (node (ref "J38") (pin "35") (pinfunction "GPIO3_B4/MAC_TXEN/UART1_RX_U_35") (pintype "passive"))
    )
    (net (code "151") (name "/PORT_HPD") (class "Default")
      (node (ref "J38") (pin "193") (pinfunction "PORT_HPD_193") (pintype "passive"))
    )
    (net (code "152") (name "/POWER_ON") (class "Default")
      (node (ref "J38") (pin "173") (pinfunction "POWER_ON_173") (pintype "passive"))
    )
    (net (code "153") (name "/PWR_EN") (class "Default")
      (node (ref "J38") (pin "171") (pinfunction "PWR_EN_171") (pintype "passive"))
    )
    (net (code "154") (name "/PWR_KEY_L") (class "Default")
      (node (ref "J38") (pin "187") (pinfunction "GPIO0_A5/EMMC_PWRON_U_187") (pintype "passive"))
    )
    (net (code "155") (name "/RECOVER") (class "Default")
      (node (ref "J38") (pin "122") (pinfunction "ADC_IN1_122") (pintype "passive"))
    )
    (net (code "156") (name "/RESET_L") (class "Default")
      (node (ref "J38") (pin "181") (pinfunction "NPOR_U_181") (pintype "passive"))
    )
    (net (code "157") (name "/RTC_CLKO_WIFI") (class "Default")
      (node (ref "J38") (pin "237") (pinfunction "RTC_CLKO_WIFI_237") (pintype "passive"))
    )
    (net (code "158") (name "/RTC_CLK_OUT") (class "Default")
      (node (ref "J38") (pin "201") (pinfunction "RTC_CLK_OUT_201") (pintype "passive"))
    )
    (net (code "159") (name "/SDIO0_CLK") (class "Default")
      (node (ref "J38") (pin "227") (pinfunction "GPIO2_D1/SDIO0_CLKOUT/TEST_CLKOUT1_U_227") (pintype "passive"))
    )
    (net (code "160") (name "/SDIO0_CMD") (class "Default")
      (node (ref "J38") (pin "229") (pinfunction "GPIO2_D0/SDIO0_CMD_U_229") (pintype "passive"))
    )
    (net (code "161") (name "/SDIO0_D0") (class "Default")
      (node (ref "J38") (pin "221") (pinfunction "GPIO2_C4/SDIO0_D0/SPI5_RXD_U_221") (pintype "passive"))
    )
    (net (code "162") (name "/SDIO0_D1") (class "Default")
      (node (ref "J38") (pin "219") (pinfunction "GPIO2_C5/SDIO0_D1/SPI5_TXD_U_219") (pintype "passive"))
    )
    (net (code "163") (name "/SDIO0_D2") (class "Default")
      (node (ref "J38") (pin "223") (pinfunction "GPIO2_C6/SDIO0_D2/SPI5_CLK_U_223") (pintype "passive"))
    )
    (net (code "164") (name "/SDIO0_D3") (class "Default")
      (node (ref "J38") (pin "225") (pinfunction "GPIO2_C7/SDIO0_D3/SPI5_CSN0_U_225") (pintype "passive"))
    )
    (net (code "165") (name "/SDMMC0_CLK") (class "Default")
      (node (ref "J38") (pin "92") (pinfunction "GPIO4_B4/SDMMC0_CLKOUT/MUCJTAG_TCK_D_92") (pintype "passive"))
    )
    (net (code "166") (name "/SDMMC0_CMD") (class "Default")
      (node (ref "J38") (pin "90") (pinfunction "GPIO4_B5/SDMMC0_CMD/MCUJTAG_TMS_U_90") (pintype "passive"))
    )
    (net (code "167") (name "/SDMMC0_D0") (class "Default")
      (node (ref "J38") (pin "94") (pinfunction "GPIO4_B0/SDMMC0_D0/UART2A_RX_U_94") (pintype "passive"))
    )
    (net (code "168") (name "/SDMMC0_D1") (class "Default")
      (node (ref "J38") (pin "96") (pinfunction "GPIO4_B1/SDMMC0_D1/UART2A_TX_U_96") (pintype "passive"))
    )
    (net (code "169") (name "/SDMMC0_D2") (class "Default")
      (node (ref "J38") (pin "86") (pinfunction "GPIO4_B2/SDMMC0_D2/APJTAG_TCK_U_86") (pintype "passive"))
    )
    (net (code "170") (name "/SDMMC0_D3") (class "Default")
      (node (ref "J38") (pin "88") (pinfunction "GPIO4_B3/SDMMC0_D3/APJTAG_TMS_U_88") (pintype "passive"))
    )
    (net (code "171") (name "/SDMMC0_DET_L") (class "Default")
      (node (ref "J38") (pin "84") (pinfunction "GPIO0_A7/SDMMC0_DET_U_84") (pintype "passive"))
    )
    (net (code "172") (name "/SDPWR_EN") (class "Default")
      (node (ref "J38") (pin "165") (pinfunction "GPIO1_C4/I2C8_SDA_U_165") (pintype "passive"))
    )
    (net (code "173") (name "/SPI1_CLK{slash}GPIO1_B1_U") (class "Default")
      (node (ref "J38") (pin "103") (pinfunction "GPIO1_B1/SPI1_CLK/PMCU_JTAG_TCK_U_103") (pintype "passive"))
    )
    (net (code "174") (name "/SPI1_CSn0{slash}GPIO1_B2_U") (class "Default")
      (node (ref "J38") (pin "105") (pinfunction "GPIO1_B2/SPI1_CSN0/PMCU_JTAG_TMS_U_105") (pintype "passive"))
    )
    (net (code "175") (name "/SPI1_RXD{slash}UART4_RX") (class "Default")
      (node (ref "J38") (pin "99") (pinfunction "GPIO1_A7/SPI1_RXD/UART4_RX_U_99") (pintype "passive"))
    )
    (net (code "176") (name "/SPI1_TXD{slash}UART4_TX") (class "Default")
      (node (ref "J38") (pin "101") (pinfunction "GPIO1_B0/SPI1_TXD/UART4_TX_U_101") (pintype "passive"))
    )
    (net (code "177") (name "/TP_INT") (class "Default")
      (node (ref "J38") (pin "255") (pinfunction "GPIO4_D3_D_255") (pintype "passive"))
    )
    (net (code "178") (name "/TP_INT1") (class "Default")
      (node (ref "J38") (pin "247") (pinfunction "GPIO4_D4_D_247") (pintype "passive"))
    )
    (net (code "179") (name "/TP_RST_1.8V") (class "Default")
      (node (ref "J38") (pin "82") (pinfunction "GPIO0_B4/TCPD_VBUS_BDIS_D_82") (pintype "passive"))
    )
    (net (code "180") (name "/TYPEC0_DM") (class "Default")
      (node (ref "J38") (pin "182") (pinfunction "TYPEC0_DM_182") (pintype "passive"))
    )
    (net (code "181") (name "/TYPEC0_DP") (class "Default")
      (node (ref "J38") (pin "184") (pinfunction "TYPEC0_DP_184") (pintype "passive"))
    )
    (net (code "182") (name "/TYPEC0_ID") (class "Default")
      (node (ref "J38") (pin "245") (pinfunction "TYPEC0_ID_245") (pintype "passive"))
      (node (ref "TP15") (pin "1") (pinfunction "1_1") (pintype "passive"))
    )
    (net (code "183") (name "/TYPEC0_RX1N") (class "Default")
      (node (ref "J38") (pin "192") (pinfunction "TYPEC0_RX1M_192") (pintype "passive"))
    )
    (net (code "184") (name "/TYPEC0_RX1P") (class "Default")
      (node (ref "J38") (pin "190") (pinfunction "TYPEC0_RX1P_190") (pintype "passive"))
    )
    (net (code "185") (name "/TYPEC0_RX2N") (class "Default")
      (node (ref "J38") (pin "180") (pinfunction "TYPEC0_RX2M_180") (pintype "passive"))
    )
    (net (code "186") (name "/TYPEC0_RX2P") (class "Default")
      (node (ref "J38") (pin "178") (pinfunction "TYPEC0_RX2P_178") (pintype "passive"))
    )
    (net (code "187") (name "/TYPEC0_SBU1") (class "Default")
      (node (ref "J38") (pin "194") (pinfunction "TYPEC0_AUXP_194") (pintype "passive"))
    )
    (net (code "188") (name "/TYPEC0_SBU1_DC") (class "Default")
      (node (ref "J38") (pin "200") (pinfunction "TYPEC0_AUXP_PD_PU_200") (pintype "passive"))
    )
    (net (code "189") (name "/TYPEC0_SBU2") (class "Default")
      (node (ref "J38") (pin "196") (pinfunction "TYPEC0_AUXM_196") (pintype "passive"))
    )
    (net (code "190") (name "/TYPEC0_SBU2_DC") (class "Default")
      (node (ref "J38") (pin "198") (pinfunction "TYPEC0_AUXM_PU_PD_198") (pintype "passive"))
    )
    (net (code "191") (name "/TYPEC0_TX1N") (class "Default")
      (node (ref "J38") (pin "186") (pinfunction "TYPEC0_TX1M_186") (pintype "passive"))
    )
    (net (code "192") (name "/TYPEC0_TX1P") (class "Default")
      (node (ref "J38") (pin "188") (pinfunction "TYPEC0_TX1P_188") (pintype "passive"))
    )
    (net (code "193") (name "/TYPEC0_TX2N") (class "Default")
      (node (ref "J38") (pin "174") (pinfunction "TYPEC0_TX2M_174") (pintype "passive"))
    )
    (net (code "194") (name "/TYPEC0_TX2P") (class "Default")
      (node (ref "J38") (pin "176") (pinfunction "TYPEC0_TX2P_176") (pintype "passive"))
    )
    (net (code "195") (name "/TYPEC0_U2VBUSDET") (class "Default")
      (node (ref "J38") (pin "106") (pinfunction "TYPEC0_U2VBUSDET_106") (pintype "passive"))
    )
    (net (code "196") (name "/TYPEC1_ID") (class "Default")
      (node (ref "J38") (pin "243") (pinfunction "TYPEC1_ID_243") (pintype "passive"))
      (node (ref "TP14") (pin "1") (pinfunction "1_1") (pintype "passive"))
    )
    (net (code "197") (name "/TYPEC1_RX2N") (class "Default")
      (node (ref "J38") (pin "154") (pinfunction "TYPEC1_RX2M_154") (pintype "passive"))
    )
    (net (code "198") (name "/TYPEC1_RX2P") (class "Default")
      (node (ref "J38") (pin "152") (pinfunction "TYPEC1_RX2P_152") (pintype "passive"))
    )
    (net (code "199") (name "/TYPEC1_SBU1") (class "Default")
      (node (ref "J38") (pin "140") (pinfunction "TYPEC1_AUXP_140") (pintype "passive"))
    )
    (net (code "200") (name "/TYPEC1_SBU1_DC") (class "Default")
      (node (ref "J38") (pin "158") (pinfunction "TYPEC1_AUXP_PD_PU_158") (pintype "passive"))
    )
    (net (code "201") (name "/TYPEC1_SBU2") (class "Default")
      (node (ref "J38") (pin "142") (pinfunction "TYPEC1_AUXM_142") (pintype "passive"))
    )
    (net (code "202") (name "/TYPEC1_SBU2_DC") (class "Default")
      (node (ref "J38") (pin "160") (pinfunction "TYPEC1_AUXM_PU_PD_160") (pintype "passive"))
    )
    (net (code "203") (name "/TYPEC1_TX2N") (class "Default")
      (node (ref "J38") (pin "146") (pinfunction "TYPEC1_TX2M_146") (pintype "passive"))
    )
    (net (code "204") (name "/TYPEC1_TX2P") (class "Default")
      (node (ref "J38") (pin "148") (pinfunction "TYPEC1_TX2P_148") (pintype "passive"))
    )
    (net (code "205") (name "/TYPEC1_U2VBUSDET") (class "Default")
      (node (ref "J38") (pin "108") (pinfunction "TYPEC1_U2VBUSDET_108") (pintype "passive"))
    )
    (net (code "206") (name "/UART0_CTS") (class "Default")
      (node (ref "J38") (pin "211") (pinfunction "GPIO2_C2/UART0_CTSN_U_211") (pintype "passive"))
    )
    (net (code "207") (name "/UART0_RTS") (class "Default")
      (node (ref "J38") (pin "209") (pinfunction "GPIO2_C3/UART0_RTSN_U_209") (pintype "passive"))
    )
    (net (code "208") (name "/UART0_RXD") (class "Default")
      (node (ref "J38") (pin "215") (pinfunction "GPIO2_C0/UART0_RX_U_215") (pintype "passive"))
    )
    (net (code "209") (name "/UART0_TXD") (class "Default")
      (node (ref "J38") (pin "213") (pinfunction "GPIO2_C1/UART0_TX_U_213") (pintype "passive"))
    )
    (net (code "210") (name "/UART2DBG_RX") (class "Default")
      (node (ref "J38") (pin "253") (pinfunction "GPIO4_C3/UART2C_RX_U_253") (pintype "passive"))
    )
    (net (code "211") (name "/UART2DBG_TX") (class "Default")
      (node (ref "J38") (pin "251") (pinfunction "GPIO4_C4/UART2C_TX_U_251") (pintype "passive"))
    )
    (net (code "212") (name "/USB3_DM") (class "Default")
      (node (ref "J38") (pin "172") (pinfunction "TYPEC1_DM_172") (pintype "passive"))
    )
    (net (code "213") (name "/USB3_DP") (class "Default")
      (node (ref "J38") (pin "170") (pinfunction "TYPEC1_DP_170") (pintype "passive"))
    )
    (net (code "214") (name "/USB3_SSRXN") (class "Default")
      (node (ref "J38") (pin "168") (pinfunction "TYPEC1_TX1M_168") (pintype "passive"))
    )
    (net (code "215") (name "/USB3_SSRXP") (class "Default")
      (node (ref "J38") (pin "166") (pinfunction "TYPEC1_TX1P_166") (pintype "passive"))
    )
    (net (code "216") (name "/USB3_SSTXN") (class "Default")
      (node (ref "J38") (pin "162") (pinfunction "TYPEC1_RX1M_162") (pintype "passive"))
    )
    (net (code "217") (name "/USB3_SSTXP") (class "Default")
      (node (ref "J38") (pin "164") (pinfunction "TYPEC1_RX1P_164") (pintype "passive"))
    )
    (net (code "218") (name "/VCC5V0_HOST_EN") (class "Default")
      (node (ref "J38") (pin "104") (pinfunction "GPIO1_A0/ISP0_SHUTTER_EN/ISP1_SHUTTER_EN/TCPD_VBUS_SINK_EN_D_104") (pintype "passive"))
    )
    (net (code "219") (name "/VCC5V0_TYPEC0_EN") (class "Default")
      (node (ref "J38") (pin "102") (pinfunction "GPIO1_A3/ISP0_FLASHTRIGOUT/ISP1_FLASHTRIGOUT_D_102") (pintype "passive"))
    )
    (net (code "220") (name "/WIFI_HOST_WAKE_L") (class "Default")
      (node (ref "J38") (pin "231") (pinfunction "GPIO0_A3/SDIO0_WRPT_D_231") (pintype "passive"))
    )
    (net (code "221") (name "/WIFI_REG_ON_H") (class "Default")
      (node (ref "J38") (pin "233") (pinfunction "GPIO0_B2_D_233") (pintype "passive"))
    )
    (net (code "222") (name "/WK2124_INT") (class "Default")
      (node (ref "J38") (pin "199") (pinfunction "GPIO1_A2/ISP0_FLASHTRIGIN/ISP1_FLASHTRIGIN/TCPD_CC1_VCONN_EN_D_199") (pintype "passive"))
    )
    (net (code "223") (name "/WK2124_RST") (class "Default")
      (node (ref "J38") (pin "163") (pinfunction "GPIO1_C1/SPI3_CLK_D_163") (pintype "passive"))
    )
    (net (code "224") (name "GND") (class "Default")
      (node (ref "C330") (pin "2") (pinfunction "2_2") (pintype "passive"))
      (node (ref "C331") (pin "2") (pinfunction "2_2") (pintype "passive"))
      (node (ref "C332") (pin "2") (pinfunction "2_2") (pintype "passive"))
      (node (ref "C333") (pin "2") (pinfunction "2_2") (pintype "passive"))
      (node (ref "C334") (pin "2") (pinfunction "2_2") (pintype "passive"))
      (node (ref "C335") (pin "2") (pinfunction "2_2") (pintype "passive"))
      (node (ref "C336") (pin "2") (pinfunction "2_2") (pintype "passive"))
      (node (ref "C337") (pin "2") (pinfunction "2_2") (pintype "passive"))
      (node (ref "C338") (pin "2") (pinfunction "2_2") (pintype "passive"))
      (node (ref "C339") (pin "2") (pinfunction "2_2") (pintype "passive"))
      (node (ref "C340") (pin "2") (pinfunction "2_2") (pintype "passive"))
      (node (ref "C341") (pin "2") (pinfunction "2_2") (pintype "passive"))
      (node (ref "C342") (pin "2") (pinfunction "2_2") (pintype "passive"))
      (node (ref "C343") (pin "2") (pinfunction "2_2") (pintype "passive"))
      (node (ref "C344") (pin "2") (pinfunction "2_2") (pintype "passive"))
      (node (ref "C345") (pin "2") (pinfunction "2_2") (pintype "passive"))
      (node (ref "C346") (pin "2") (pinfunction "2_2") (pintype "passive"))
      (node (ref "C347") (pin "2") (pinfunction "2_2") (pintype "passive"))
      (node (ref "C350") (pin "2") (pinfunction "2_2") (pintype "passive"))
      (node (ref "C351") (pin "2") (pinfunction "2_2") (pintype "passive"))
      (node (ref "C352") (pin "2") (pinfunction "2_2") (pintype "passive"))
      (node (ref "C353") (pin "2") (pinfunction "2_2") (pintype "passive"))
      (node (ref "J38") (pin "10") (pinfunction "GND_25_10") (pintype "passive"))
      (node (ref "J38") (pin "107") (pinfunction "GND_7_107") (pintype "passive"))
      (node (ref "J38") (pin "113") (pinfunction "GND_8_113") (pintype "passive"))
      (node (ref "J38") (pin "119") (pinfunction "GND_9_119") (pintype "passive"))
      (node (ref "J38") (pin "12") (pinfunction "GND_26_12") (pintype "passive"))
      (node (ref "J38") (pin "125") (pinfunction "GND_10_125") (pintype "passive"))
      (node (ref "J38") (pin "126") (pinfunction "GND_37_126") (pintype "passive"))
      (node (ref "J38") (pin "131") (pinfunction "GND_11_131") (pintype "passive"))
      (node (ref "J38") (pin "132") (pinfunction "GND_38_132") (pintype "passive"))
      (node (ref "J38") (pin "137") (pinfunction "GND_12_137") (pintype "passive"))
      (node (ref "J38") (pin "138") (pinfunction "GND_39_138") (pintype "passive"))
      (node (ref "J38") (pin "14") (pinfunction "GND_27_14") (pintype "passive"))
      (node (ref "J38") (pin "143") (pinfunction "GND_13_143") (pintype "passive"))
      (node (ref "J38") (pin "144") (pinfunction "GND_40_144") (pintype "passive"))
      (node (ref "J38") (pin "149") (pinfunction "GND_14_149") (pintype "passive"))
      (node (ref "J38") (pin "150") (pinfunction "GND_41_150") (pintype "passive"))
      (node (ref "J38") (pin "155") (pinfunction "GND_15_155") (pintype "passive"))
      (node (ref "J38") (pin "156") (pinfunction "GND_42_156") (pintype "passive"))
      (node (ref "J38") (pin "16") (pinfunction "GND_28_16") (pintype "passive"))
      (node (ref "J38") (pin "161") (pinfunction "GND_16_161") (pintype "passive"))
      (node (ref "J38") (pin "18") (pinfunction "GND_29_18") (pintype "passive"))
      (node (ref "J38") (pin "19") (pinfunction "GND_1_19") (pintype "passive"))
      (node (ref "J38") (pin "2") (pinfunction "GND_21_2") (pintype "passive"))
      (node (ref "J38") (pin "202") (pinfunction "GND_43_202") (pintype "passive"))
      (node (ref "J38") (pin "203") (pinfunction "GND_17_203") (pintype "passive"))
      (node (ref "J38") (pin "220") (pinfunction "GND_44_220") (pintype "passive"))
      (node (ref "J38") (pin "226") (pinfunction "GND_45_226") (pintype "passive"))
      (node (ref "J38") (pin "232") (pinfunction "GND_46_232") (pintype "passive"))
      (node (ref "J38") (pin "235") (pinfunction "GND_18_235") (pintype "passive"))
      (node (ref "J38") (pin "238") (pinfunction "GND_47_238") (pintype "passive"))
      (node (ref "J38") (pin "244") (pinfunction "GND_48_244") (pintype "passive"))
      (node (ref "J38") (pin "250") (pinfunction "GND_49_250") (pintype "passive"))
      (node (ref "J38") (pin "256") (pinfunction "GND_50_256") (pintype "passive"))
      (node (ref "J38") (pin "262") (pinfunction "GND_51_262") (pintype "passive"))
      (node (ref "J38") (pin "268") (pinfunction "GND_52_268") (pintype "passive"))
      (node (ref "J38") (pin "274") (pinfunction "GND_53_274") (pintype "passive"))
      (node (ref "J38") (pin "275") (pinfunction "GND_19_275") (pintype "passive"))
      (node (ref "J38") (pin "280") (pinfunction "GND_54_280") (pintype "passive"))
      (node (ref "J38") (pin "286") (pinfunction "GND_55_286") (pintype "passive"))
      (node (ref "J38") (pin "292") (pinfunction "GND_56_292") (pintype "passive"))
      (node (ref "J38") (pin "298") (pinfunction "GND_57_298") (pintype "passive"))
      (node (ref "J38") (pin "304") (pinfunction "GND_58_304") (pintype "passive"))
      (node (ref "J38") (pin "305") (pinfunction "GND_20_305") (pintype "passive"))
      (node (ref "J38") (pin "310") (pinfunction "NC_1_310") (pintype "passive"))
      (node (ref "J38") (pin "313") (pinfunction "GND_59_313") (pintype "passive"))
      (node (ref "J38") (pin "314") (pinfunction "GND_60_314") (pintype "passive"))
      (node (ref "J38") (pin "315") (pinfunction "GND_61_315") (pintype "passive"))
      (node (ref "J38") (pin "316") (pinfunction "GND_62_316") (pintype "passive"))
      (node (ref "J38") (pin "317") (pinfunction "GND_63_317") (pintype "passive"))
      (node (ref "J38") (pin "318") (pinfunction "GND_64_318") (pintype "passive"))
      (node (ref "J38") (pin "32") (pinfunction "GND_30_32") (pintype "passive"))
      (node (ref "J38") (pin "33") (pinfunction "GND_2_33") (pintype "passive"))
      (node (ref "J38") (pin "4") (pinfunction "GND_22_4") (pintype "passive"))
      (node (ref "J38") (pin "46") (pinfunction "GND_65_46") (pintype "passive"))
      (node (ref "J38") (pin "47") (pinfunction "GND_3_47") (pintype "passive"))
      (node (ref "J38") (pin "52") (pinfunction "GND_31_52") (pintype "passive"))
      (node (ref "J38") (pin "58") (pinfunction "GND_32_58") (pintype "passive"))
      (node (ref "J38") (pin "6") (pinfunction "GND_23_6") (pintype "passive"))
      (node (ref "J38") (pin "61") (pinfunction "GND_4_61") (pintype "passive"))
      (node (ref "J38") (pin "64") (pinfunction "GND_33_64") (pintype "passive"))
      (node (ref "J38") (pin "70") (pinfunction "GND_34_70") (pintype "passive"))
      (node (ref "J38") (pin "76") (pinfunction "GND_35_76") (pintype "passive"))
      (node (ref "J38") (pin "8") (pinfunction "GND_24_8") (pintype "passive"))
      (node (ref "J38") (pin "80") (pinfunction "GND_66_80") (pintype "passive"))
      (node (ref "J38") (pin "85") (pinfunction "GND_5_85") (pintype "passive"))
      (node (ref "J38") (pin "91") (pinfunction "GND_6_91") (pintype "passive"))
    )
    (net (code "225") (name "Net-(J38-VCCA(3V-5V))") (class "Default")
      (node (ref "J38") (pin "97") (pinfunction "VCCA(3V-5V)_97") (pintype "passive"))
      (node (ref "TP13") (pin "1") (pinfunction "1_1") (pintype "passive"))
    )
    (net (code "226") (name "VCC1V8_DVP") (class "Default")
      (node (ref "C344") (pin "1") (pinfunction "1_1") (pintype "passive"))
      (node (ref "C345") (pin "1") (pinfunction "1_1") (pintype "passive"))
      (node (ref "J38") (pin "93") (pinfunction "VCC1V8_DVP_93") (pintype "passive"))
    )
    (net (code "227") (name "VCC2V8_DVP") (class "Default")
      (node (ref "C346") (pin "1") (pinfunction "1_1") (pintype "passive"))
      (node (ref "C347") (pin "1") (pinfunction "1_1") (pintype "passive"))
      (node (ref "J38") (pin "95") (pinfunction "VCC2V8_DVP_95") (pintype "passive"))
    )
    (net (code "228") (name "VCC3V3_S3") (class "Default")
      (node (ref "C336") (pin "1") (pinfunction "1_1") (pintype "passive"))
      (node (ref "C337") (pin "1") (pinfunction "1_1") (pintype "passive"))
      (node (ref "J38") (pin "26") (pinfunction "VCC3V3_S3_1_26") (pintype "passive"))
      (node (ref "J38") (pin "28") (pinfunction "VCC3V3_S3_2_28") (pintype "passive"))
      (node (ref "J38") (pin "30") (pinfunction "VCC3V3_S3_3_30") (pintype "passive"))
    )
    (net (code "229") (name "VCC3V3_SYS") (class "Default")
      (node (ref "C334") (pin "1") (pinfunction "1_1") (pintype "passive"))
      (node (ref "C335") (pin "1") (pinfunction "1_1") (pintype "passive"))
      (node (ref "J38") (pin "20") (pinfunction "VCC3V3_SYS_1_20") (pintype "passive"))
      (node (ref "J38") (pin "22") (pinfunction "VCC3V3_SYS_2_22") (pintype "passive"))
      (node (ref "J38") (pin "24") (pinfunction "VCC3V3_SYS_3_24") (pintype "passive"))
    )
    (net (code "230") (name "VCCA1V8_CODEC") (class "Default")
      (node (ref "C352") (pin "1") (pinfunction "1_1") (pintype "passive"))
      (node (ref "C353") (pin "1") (pinfunction "1_1") (pintype "passive"))
      (node (ref "J38") (pin "271") (pinfunction "VCCA1V8_CODEC_1_271") (pintype "passive"))
      (node (ref "J38") (pin "273") (pinfunction "VCCA1V8_CODEC_2_273") (pintype "passive"))
    )
    (net (code "231") (name "VCCA1V8_S3") (class "Default")
      (node (ref "C342") (pin "1") (pinfunction "1_1") (pintype "passive"))
      (node (ref "C343") (pin "1") (pinfunction "1_1") (pintype "passive"))
      (node (ref "J38") (pin "44") (pinfunction "VCCA1V8_S3_44") (pintype "passive"))
    )
    (net (code "232") (name "VCCA3V0_CODEC") (class "Default")
      (node (ref "C350") (pin "1") (pinfunction "1_1") (pintype "passive"))
      (node (ref "C351") (pin "1") (pinfunction "1_1") (pintype "passive"))
      (node (ref "J38") (pin "267") (pinfunction "VCCA3V0_CODEC_1_267") (pintype "passive"))
      (node (ref "J38") (pin "269") (pinfunction "VCCA3V0_CODEC_2_269") (pintype "passive"))
    )
    (net (code "233") (name "VCC_1V8") (class "Default")
      (node (ref "C340") (pin "1") (pinfunction "1_1") (pintype "passive"))
      (node (ref "C341") (pin "1") (pinfunction "1_1") (pintype "passive"))
      (node (ref "J38") (pin "38") (pinfunction "VCC_1V8_1_38") (pintype "passive"))
      (node (ref "J38") (pin "40") (pinfunction "VCC_1V8_2_40") (pintype "passive"))
    )
    (net (code "234") (name "VCC_3V0") (class "Default")
      (node (ref "C338") (pin "1") (pinfunction "1_1") (pintype "passive"))
      (node (ref "C339") (pin "1") (pinfunction "1_1") (pintype "passive"))
      (node (ref "J38") (pin "34") (pinfunction "VCC_3V0_1_34") (pintype "passive"))
      (node (ref "J38") (pin "36") (pinfunction "VCC_3V0_2_36") (pintype "passive"))
    )
    (net (code "235") (name "VCC_RTC") (class "Default")
      (node (ref "J38") (pin "42") (pinfunction "VCC_RTC_42") (pintype "passive"))
    )
    (net (code "236") (name "VCC_SYS") (class "Default")
      (node (ref "C330") (pin "1") (pinfunction "1_1") (pintype "passive"))
      (node (ref "C331") (pin "1") (pinfunction "1_1") (pintype "passive"))
      (node (ref "C332") (pin "1") (pinfunction "1_1") (pintype "passive"))
      (node (ref "C333") (pin "1") (pinfunction "1_1") (pintype "passive"))
      (node (ref "J38") (pin "1") (pinfunction "VCC_SYS_1_1") (pintype "passive"))
      (node (ref "J38") (pin "11") (pinfunction "VCC_SYS_6_11") (pintype "passive"))
      (node (ref "J38") (pin "13") (pinfunction "VCC_SYS_7_13") (pintype "passive"))
      (node (ref "J38") (pin "15") (pinfunction "VCC_SYS_8_15") (pintype "passive"))
      (node (ref "J38") (pin "17") (pinfunction "VCC_SYS_9_17") (pintype "passive"))
      (node (ref "J38") (pin "3") (pinfunction "VCC_SYS_2_3") (pintype "passive"))
      (node (ref "J38") (pin "5") (pinfunction "VCC_SYS_3_5") (pintype "passive"))
      (node (ref "J38") (pin "7") (pinfunction "VCC_SYS_4_7") (pintype "passive"))
      (node (ref "J38") (pin "9") (pinfunction "VCC_SYS_5_9") (pintype "passive"))
    )
    (net (code "237") (name "unconnected-(J38-NC_2-Pad312)") (class "Default")
      (node (ref "J38") (pin "312") (pinfunction "NC_2_312") (pintype "passive"))
    )
  )
)
